# CC2530.net
KiCad netlist of a schematic drawn in Altium Designer
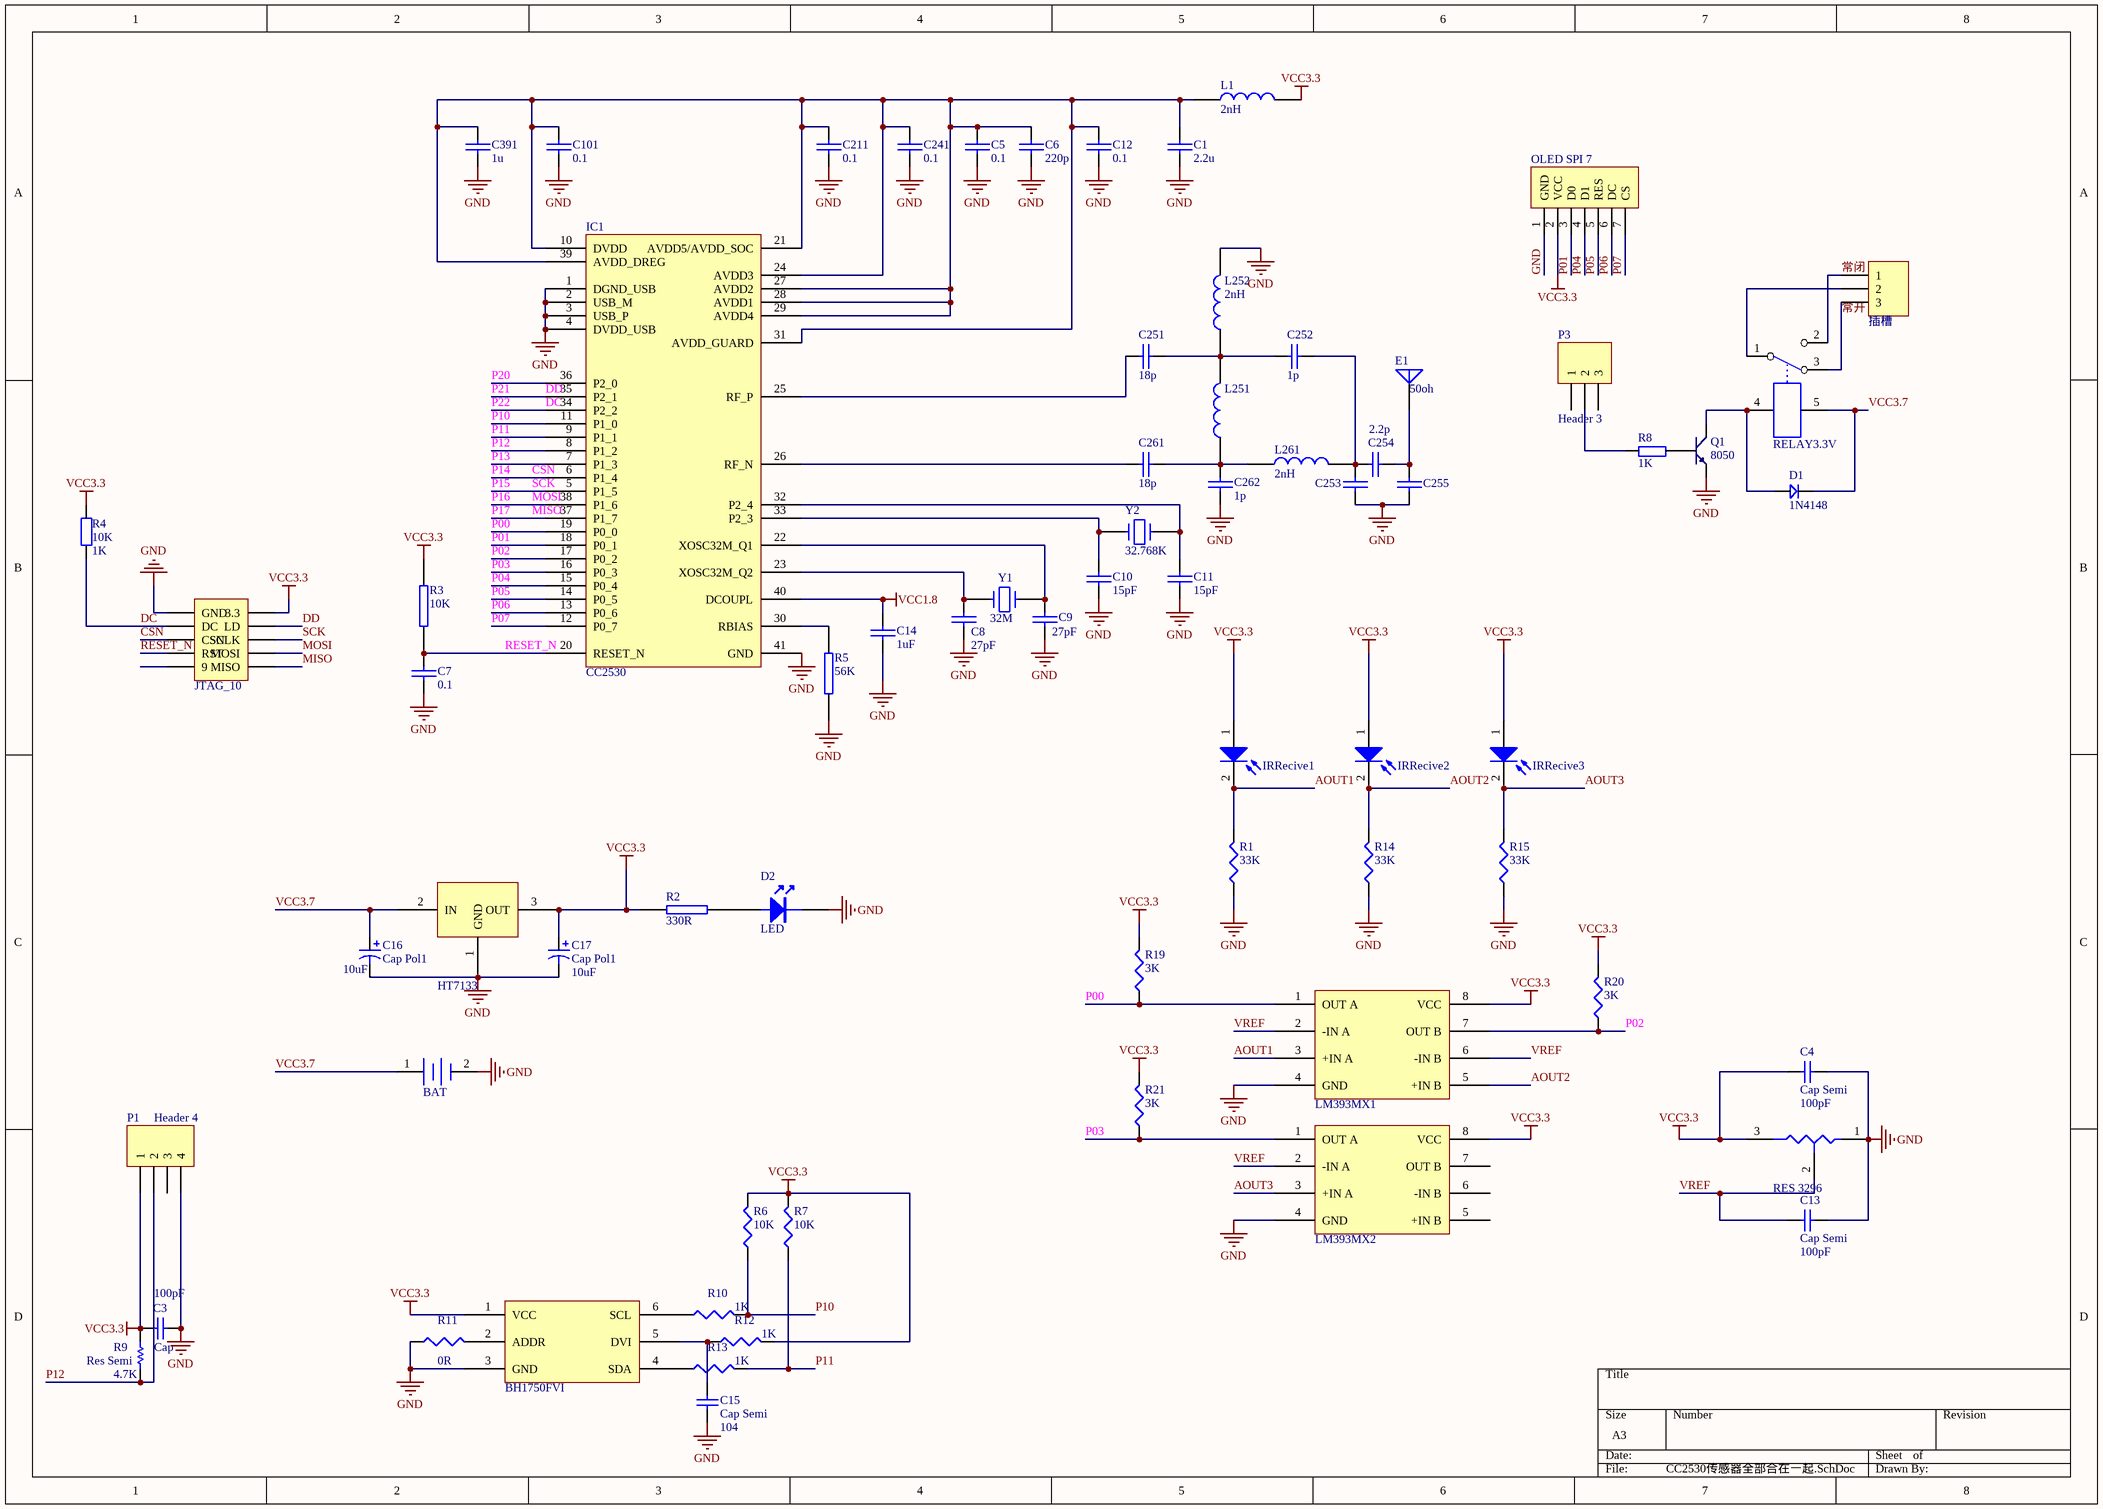
[diagram p0: CC2530传感器全部合在一起.SchDoc]

(export (version "E")
  (design (tool "Eeschema 10.0.6"))
  (components
    (comp (ref "BAT") (value "BAT") (footprint "BAT") (libsource (lib "my Integrated lib ") (part "BAT")))
    (comp (ref "BH1750FVI")
      (value "BH1750FVI")
      (footprint "BH1750FVI")
      (libsource (lib "my Integrated lib ") (part "BH1750FVI"))
    )
    (comp (ref "C1")
      (value "2.2u")
      (footprint "J1-0603")
      (description "Capacitor")
      (libsource (lib "Miscellaneous Devices") (part "CAP"))
    )
    (comp (ref "C3")
      (value "Cap")
      (footprint "J1-0603")
      (description "Capacitor")
      (fields (field (name "ALTIUM_VALUE") "100pF") (field (name "PUBLISHER") "Altium Limited"))
      (libsource (lib "Miscellaneous Devices") (part "Cap"))
    )
    (comp (ref "C4")
      (value "Cap Semi")
      (footprint "3.5X2.8X1.9")
      (description "Capacitor (Semiconductor SIM Model)")
      (fields (field (name "ALTIUM_VALUE") "100pF") (field (name "PUBLISHER") "Altium Limited"))
      (libsource (lib "Miscellaneous Devices") (part "Cap Semi"))
    )
    (comp (ref "C5")
      (value "0.1")
      (footprint "J1-0603")
      (description "Capacitor")
      (libsource (lib "Miscellaneous Devices") (part "CAP"))
    )
    (comp (ref "C6")
      (value "220p")
      (footprint "J1-0603")
      (description "Capacitor")
      (libsource (lib "Miscellaneous Devices") (part "CAP"))
    )
    (comp (ref "C7")
      (value "0.1")
      (footprint "J1-0603")
      (description "Capacitor")
      (libsource (lib "Miscellaneous Devices") (part "CAP"))
    )
    (comp (ref "C8")
      (value "27pF")
      (footprint "J1-0603")
      (description "Capacitor")
      (libsource (lib "Miscellaneous Devices") (part "CAP"))
    )
    (comp (ref "C9")
      (value "27pF")
      (footprint "J1-0603")
      (description "Capacitor")
      (libsource (lib "Miscellaneous Devices") (part "CAP"))
    )
    (comp (ref "C10")
      (value "15pF")
      (footprint "J1-0603")
      (description "Capacitor")
      (libsource (lib "Miscellaneous Devices") (part "CAP"))
    )
    (comp (ref "C11")
      (value "15pF")
      (footprint "J1-0603")
      (description "Capacitor")
      (libsource (lib "Miscellaneous Devices") (part "CAP"))
    )
    (comp (ref "C12")
      (value "0.1")
      (footprint "J1-0603")
      (description "Capacitor")
      (libsource (lib "Miscellaneous Devices") (part "CAP"))
    )
    (comp (ref "C13")
      (value "Cap Semi")
      (footprint "3.5X2.8X1.9")
      (description "Capacitor (Semiconductor SIM Model)")
      (fields (field (name "ALTIUM_VALUE") "100pF") (field (name "PUBLISHER") "Altium Limited"))
      (libsource (lib "Miscellaneous Devices") (part "Cap Semi"))
    )
    (comp (ref "C14")
      (value "1uF")
      (footprint "J1-0603")
      (description "Capacitor")
      (libsource (lib "Miscellaneous Devices") (part "CAP"))
    )
    (comp (ref "C15")
      (value "Cap Semi")
      (footprint "3.5X2.8X1.9")
      (description "Capacitor (Semiconductor SIM Model)")
      (fields (field (name "ALTIUM_VALUE") "104") (field (name "PUBLISHER") "Altium Limited"))
      (libsource (lib "Miscellaneous Devices") (part "Cap Semi"))
    )
    (comp (ref "C16")
      (value "Cap Pol1")
      (footprint "3.5X2.8X1.9")
      (description "Polarized Capacitor (Radial)")
      (fields (field (name "ALTIUM_VALUE") "10uF") (field (name "PUBLISHER") "Altium Limited"))
      (libsource (lib "Miscellaneous Devices") (part "Cap Pol1"))
    )
    (comp (ref "C17")
      (value "Cap Pol1")
      (footprint "3.5X2.8X1.9")
      (description "Polarized Capacitor (Radial)")
      (fields (field (name "ALTIUM_VALUE") "10uF") (field (name "PUBLISHER") "Altium Limited"))
      (libsource (lib "Miscellaneous Devices") (part "Cap Pol1"))
    )
    (comp (ref "C101")
      (value "0.1")
      (footprint "J1-0603")
      (description "Capacitor")
      (libsource (lib "Miscellaneous Devices") (part "CAP"))
    )
    (comp (ref "C211")
      (value "0.1")
      (footprint "J1-0603")
      (description "Capacitor")
      (libsource (lib "Miscellaneous Devices") (part "CAP"))
    )
    (comp (ref "C241")
      (value "0.1")
      (footprint "J1-0603")
      (description "Capacitor")
      (libsource (lib "Miscellaneous Devices") (part "CAP"))
    )
    (comp (ref "C251")
      (value "18p")
      (footprint "J1-0603")
      (description "Capacitor")
      (libsource (lib "Miscellaneous Devices") (part "CAP"))
    )
    (comp (ref "C252")
      (value "1p")
      (footprint "J1-0603")
      (description "Capacitor")
      (libsource (lib "Miscellaneous Devices") (part "CAP"))
    )
    (comp (ref "C253")
      (value "~")
      (footprint "J1-0603")
      (description "Capacitor")
      (libsource (lib "Miscellaneous Devices") (part "CAP"))
    )
    (comp (ref "C254")
      (value "2.2p")
      (footprint "J1-0603")
      (description "Capacitor")
      (libsource (lib "Miscellaneous Devices") (part "CAP"))
    )
    (comp (ref "C255")
      (value "~")
      (footprint "J1-0603")
      (description "Capacitor")
      (libsource (lib "Miscellaneous Devices") (part "CAP"))
    )
    (comp (ref "C261")
      (value "18p")
      (footprint "J1-0603")
      (description "Capacitor")
      (libsource (lib "Miscellaneous Devices") (part "CAP"))
    )
    (comp (ref "C262")
      (value "1p")
      (footprint "J1-0603")
      (description "Capacitor")
      (libsource (lib "Miscellaneous Devices") (part "CAP"))
    )
    (comp (ref "C391")
      (value "1u")
      (footprint "J1-0603")
      (description "Capacitor")
      (libsource (lib "Miscellaneous Devices") (part "CAP"))
    )
    (comp (ref "D1") (value "1N4148") (footprint "C1206") (libsource (lib "my Integrated lib ") (part "D")))
    (comp (ref "D2")
      (value "LED")
      (footprint "3.2X1.6X1.1")
      (libsource (lib "Miscellaneous Devices") (part "LED"))
    )
    (comp (ref "E1")
      (value "50oh")
      (footprint "ANT")
      (description "Generic Antenna")
      (libsource (lib "Miscellaneous Devices") (part "ANTENNA"))
    )
    (comp (ref "HT7133")
      (value "HT7133")
      (footprint "HT7133")
      (libsource (lib "my Integrated lib ") (part "HT7133"))
    )
    (comp (ref "IC1") (value "CC2530") (footprint "QFN40_RHA") (libsource (lib "集成") (part "CC2530")))
    (comp (ref "IRRecive1")
      (value "IRRecive")
      (footprint "IRRecive")
      (libsource (lib "my Integrated lib ") (part "IRRecive"))
    )
    (comp (ref "IRRecive2")
      (value "IRRecive")
      (footprint "IRRecive")
      (libsource (lib "my Integrated lib ") (part "IRRecive"))
    )
    (comp (ref "IRRecive3")
      (value "IRRecive")
      (footprint "IRRecive")
      (libsource (lib "my Integrated lib ") (part "IRRecive"))
    )
    (comp (ref "JTAG_10")
      (value "JTAG_10")
      (footprint "JTAG_10")
      (libsource (lib "my Integrated lib ") (part "JTAG_10"))
    )
    (comp (ref "L1")
      (value "2nH")
      (footprint "J1-0603")
      (libsource (lib "Miscellaneous Devices") (part "INDUCTOR"))
    )
    (comp (ref "L251")
      (value "~")
      (footprint "J1-0603")
      (libsource (lib "Miscellaneous Devices") (part "INDUCTOR"))
    )
    (comp (ref "L252")
      (value "2nH")
      (footprint "J1-0603")
      (libsource (lib "Miscellaneous Devices") (part "INDUCTOR"))
    )
    (comp (ref "L261")
      (value "2nH")
      (footprint "J1-0603")
      (libsource (lib "Miscellaneous Devices") (part "INDUCTOR"))
    )
    (comp (ref "LM393MX1")
      (value "LM393MX")
      (footprint "LM393MX")
      (libsource (lib "my Integrated lib ") (part "LM393MX"))
    )
    (comp (ref "LM393MX2")
      (value "LM393MX")
      (footprint "LM393MX")
      (libsource (lib "my Integrated lib ") (part "LM393MX"))
    )
    (comp (ref "OLED SPI 7")
      (value "OLED SPI 7")
      (footprint "OLED SPI 7")
      (libsource (lib "my Integrated lib ") (part "OLED SPI 7"))
    )
    (comp (ref "P1")
      (value "Header 4")
      (footprint "HDR1X4")
      (description "Header, 4-Pin")
      (fields (field (name "PUBLISHER") "Altium Limited"))
      (libsource (lib "Miscellaneous Connectors") (part "Header 4"))
    )
    (comp (ref "P3")
      (value "Header 3")
      (footprint "HDR1X3")
      (description "Header, 3-Pin")
      (fields (field (name "PUBLISHER") "Altium Limited"))
      (libsource (lib "Miscellaneous Connectors") (part "Header 3"))
    )
    (comp (ref "Q1")
      (value "8050")
      (footprint "SOT-23R")
      (description "8050/BCW846/BCW847")
      (libsource (lib "my Integrated lib ") (part "NPN"))
    )
    (comp (ref "R1")
      (value "33K")
      (footprint "J1-0603")
      (description "Resistor")
      (fields (field (name "Comment") "Res3") (field (name "PUBLISHER") "Altium Limited"))
      (libsource (lib "Miscellaneous Devices") (part "Res3"))
    )
    (comp (ref "R2")
      (value "330R")
      (footprint "J1-0603")
      (libsource (lib "Miscellaneous Devices") (part "RES2"))
    )
    (comp (ref "R3")
      (value "10K")
      (footprint "J1-0603")
      (libsource (lib "Miscellaneous Devices") (part "RES2"))
    )
    (comp (ref "R4")
      (value "10K")
      (footprint "J1-0603")
      (fields (field (name "ALTIUM_VALUE") "1K"))
      (libsource (lib "集成库") (part "res0402"))
    )
    (comp (ref "R5")
      (value "56K")
      (footprint "J1-0603")
      (libsource (lib "Miscellaneous Devices") (part "RES2"))
    )
    (comp (ref "R6")
      (value "10K")
      (footprint "J1-0603")
      (description "Resistor")
      (fields (field (name "Comment") "Res3") (field (name "PUBLISHER") "Altium Limited"))
      (libsource (lib "Miscellaneous Devices") (part "Res3"))
    )
    (comp (ref "R7")
      (value "10K")
      (footprint "J1-0603")
      (description "Resistor")
      (fields (field (name "Comment") "Res3") (field (name "PUBLISHER") "Altium Limited"))
      (libsource (lib "Miscellaneous Devices") (part "Res3"))
    )
    (comp (ref "R8") (value "1K") (footprint "J1-0603") (libsource (lib "my Integrated lib ") (part "R")))
    (comp (ref "R9")
      (value "Res Semi")
      (footprint "J1-0603")
      (description "Semiconductor Resistor")
      (fields (field (name "ALTIUM_VALUE") "4.7K") (field (name "PUBLISHER") "Altium Limited"))
      (libsource (lib "Miscellaneous Devices") (part "Res Semi"))
    )
    (comp (ref "R10")
      (value "1K")
      (footprint "J1-0603")
      (description "Resistor")
      (fields (field (name "Comment") "Res3") (field (name "PUBLISHER") "Altium Limited"))
      (libsource (lib "Miscellaneous Devices") (part "Res3"))
    )
    (comp (ref "R11")
      (value "0R")
      (footprint "J1-0603")
      (description "Resistor")
      (fields (field (name "Comment") "Res3") (field (name "PUBLISHER") "Altium Limited"))
      (libsource (lib "Miscellaneous Devices") (part "Res3"))
    )
    (comp (ref "R12")
      (value "1K")
      (footprint "J1-0603")
      (description "Resistor")
      (fields (field (name "Comment") "Res3") (field (name "PUBLISHER") "Altium Limited"))
      (libsource (lib "Miscellaneous Devices") (part "Res3"))
    )
    (comp (ref "R13")
      (value "1K")
      (footprint "J1-0603")
      (description "Resistor")
      (fields (field (name "Comment") "Res3") (field (name "PUBLISHER") "Altium Limited"))
      (libsource (lib "Miscellaneous Devices") (part "Res3"))
    )
    (comp (ref "R14")
      (value "33K")
      (footprint "J1-0603")
      (description "Resistor")
      (fields (field (name "Comment") "Res3") (field (name "PUBLISHER") "Altium Limited"))
      (libsource (lib "Miscellaneous Devices") (part "Res3"))
    )
    (comp (ref "R15")
      (value "33K")
      (footprint "J1-0603")
      (description "Resistor")
      (fields (field (name "Comment") "Res3") (field (name "PUBLISHER") "Altium Limited"))
      (libsource (lib "Miscellaneous Devices") (part "Res3"))
    )
    (comp (ref "R19")
      (value "3K")
      (footprint "J1-0603")
      (description "Resistor")
      (fields (field (name "Comment") "Res3") (field (name "PUBLISHER") "Altium Limited"))
      (libsource (lib "Miscellaneous Devices") (part "Res3"))
    )
    (comp (ref "R20")
      (value "3K")
      (footprint "J1-0603")
      (description "Resistor")
      (fields (field (name "Comment") "Res3") (field (name "PUBLISHER") "Altium Limited"))
      (libsource (lib "Miscellaneous Devices") (part "Res3"))
    )
    (comp (ref "R21")
      (value "3K")
      (footprint "J1-0603")
      (description "Resistor")
      (fields (field (name "Comment") "Res3") (field (name "PUBLISHER") "Altium Limited"))
      (libsource (lib "Miscellaneous Devices") (part "Res3"))
    )
    (comp (ref "RELAY3.3V")
      (value "RELAY3.3V")
      (footprint "RELAY3.3V")
      (libsource (lib "my Integrated lib ") (part "RELAY3.3V"))
    )
    (comp (ref "RES 3296")
      (value "RES 3296")
      (footprint "RES 3296")
      (libsource (lib "my Integrated lib ") (part "RES 3296"))
    )
    (comp (ref "Y1")
      (value "32M")
      (footprint "XTAL_US")
      (description "Crystal")
      (libsource (lib "Miscellaneous Devices") (part "CRYSTAL"))
    )
    (comp (ref "Y2")
      (value "32.768K")
      (footprint "XTAL 32M")
      (description "Crystal")
      (libsource (lib "Miscellaneous Devices") (part "CRYSTAL"))
    )
    (comp (ref "插槽") (value "插槽") (footprint "杜邦线插槽") (libsource (lib "my Integrated lib ") (part "插槽")))
  )
  (nets
    (net (code "1") (name "/AOUT1") (class "Default")
      (node (ref "IRRecive1") (pin "2") (pinfunction "K_2") (pintype "passive"))
      (node (ref "LM393MX1") (pin "3") (pinfunction "+IN_A_3") (pintype "passive"))
      (node (ref "R1") (pin "2") (pinfunction "2_2") (pintype "passive"))
    )
    (net (code "2") (name "/AOUT2") (class "Default")
      (node (ref "IRRecive2") (pin "2") (pinfunction "K_2") (pintype "passive"))
      (node (ref "LM393MX1") (pin "5") (pinfunction "+IN_B_5") (pintype "passive"))
      (node (ref "R14") (pin "2") (pinfunction "2_2") (pintype "passive"))
    )
    (net (code "3") (name "/AOUT3") (class "Default")
      (node (ref "IRRecive3") (pin "2") (pinfunction "K_2") (pintype "passive"))
      (node (ref "LM393MX2") (pin "3") (pinfunction "+IN_A_3") (pintype "passive"))
      (node (ref "R15") (pin "2") (pinfunction "2_2") (pintype "passive"))
    )
    (net (code "4") (name "/CSN") (class "Default")
      (node (ref "IC1") (pin "6") (pinfunction "P1_4_6") (pintype "passive"))
      (node (ref "JTAG_10") (pin "5") (pinfunction "CSN_5") (pintype "passive"))
    )
    (net (code "5") (name "/DC") (class "Default")
      (node (ref "IC1") (pin "34") (pinfunction "P2_2_34") (pintype "passive"))
      (node (ref "JTAG_10") (pin "3") (pinfunction "DC_3") (pintype "passive"))
      (node (ref "R4") (pin "1") (pinfunction "1_1") (pintype "passive"))
    )
    (net (code "6") (name "/DD") (class "Default")
      (node (ref "IC1") (pin "35") (pinfunction "P2_1_35") (pintype "passive"))
      (node (ref "JTAG_10") (pin "4") (pinfunction "LD_4") (pintype "passive"))
    )
    (net (code "7") (name "/MISO") (class "Default")
      (node (ref "IC1") (pin "37") (pinfunction "P1_7_37") (pintype "passive"))
      (node (ref "JTAG_10") (pin "10") (pinfunction "MISO_10") (pintype "passive"))
    )
    (net (code "8") (name "/MOSI") (class "Default")
      (node (ref "IC1") (pin "38") (pinfunction "P1_6_38") (pintype "passive"))
      (node (ref "JTAG_10") (pin "8") (pinfunction "MOSI_8") (pintype "passive"))
    )
    (net (code "9") (name "/P00") (class "Default")
      (node (ref "IC1") (pin "19") (pinfunction "P0_0_19") (pintype "passive"))
      (node (ref "LM393MX1") (pin "1") (pinfunction "OUT_A_1") (pintype "passive"))
      (node (ref "R19") (pin "1") (pinfunction "1_1") (pintype "passive"))
    )
    (net (code "10") (name "/P01") (class "Default")
      (node (ref "IC1") (pin "18") (pinfunction "P0_1_18") (pintype "passive"))
      (node (ref "OLED SPI 7") (pin "3") (pinfunction "D0_3") (pintype "passive"))
    )
    (net (code "11") (name "/P02") (class "Default")
      (node (ref "IC1") (pin "17") (pinfunction "P0_2_17") (pintype "passive"))
      (node (ref "LM393MX1") (pin "7") (pinfunction "OUT_B_7") (pintype "passive"))
      (node (ref "R20") (pin "1") (pinfunction "1_1") (pintype "passive"))
    )
    (net (code "12") (name "/P03") (class "Default")
      (node (ref "IC1") (pin "16") (pinfunction "P0_3_16") (pintype "passive"))
      (node (ref "LM393MX2") (pin "1") (pinfunction "OUT_A_1") (pintype "passive"))
      (node (ref "R21") (pin "1") (pinfunction "1_1") (pintype "passive"))
    )
    (net (code "13") (name "/P04") (class "Default")
      (node (ref "IC1") (pin "15") (pinfunction "P0_4_15") (pintype "passive"))
      (node (ref "OLED SPI 7") (pin "4") (pinfunction "D1_4") (pintype "passive"))
    )
    (net (code "14") (name "/P05") (class "Default")
      (node (ref "IC1") (pin "14") (pinfunction "P0_5_14") (pintype "passive"))
      (node (ref "OLED SPI 7") (pin "5") (pinfunction "RES_5") (pintype "passive"))
    )
    (net (code "15") (name "/P06") (class "Default")
      (node (ref "IC1") (pin "13") (pinfunction "P0_6_13") (pintype "passive"))
      (node (ref "OLED SPI 7") (pin "6") (pinfunction "DC_6") (pintype "passive"))
    )
    (net (code "16") (name "/P07") (class "Default")
      (node (ref "IC1") (pin "12") (pinfunction "P0_7_12") (pintype "passive"))
      (node (ref "OLED SPI 7") (pin "7") (pinfunction "CS_7") (pintype "passive"))
    )
    (net (code "17") (name "/P10") (class "Default")
      (node (ref "IC1") (pin "11") (pinfunction "P1_0_11") (pintype "passive"))
      (node (ref "R10") (pin "2") (pinfunction "2_2") (pintype "passive"))
      (node (ref "R6") (pin "1") (pinfunction "1_1") (pintype "passive"))
    )
    (net (code "18") (name "/P11") (class "Default")
      (node (ref "IC1") (pin "9") (pinfunction "P1_1_9") (pintype "passive"))
      (node (ref "R13") (pin "2") (pinfunction "2_2") (pintype "passive"))
      (node (ref "R7") (pin "1") (pinfunction "1_1") (pintype "passive"))
    )
    (net (code "19") (name "/P12") (class "Default")
      (node (ref "IC1") (pin "8") (pinfunction "P1_2_8") (pintype "passive"))
      (node (ref "P1") (pin "2") (pinfunction "2_2") (pintype "passive"))
      (node (ref "R9") (pin "1") (pinfunction "1_1") (pintype "passive"))
    )
    (net (code "20") (name "/P13") (class "Default")
      (node (ref "IC1") (pin "7") (pinfunction "P1_3_7") (pintype "passive"))
    )
    (net (code "21") (name "/P15") (class "Default")
      (node (ref "IC1") (pin "5") (pinfunction "P1_5_5") (pintype "passive"))
      (node (ref "JTAG_10") (pin "6") (pinfunction "SCLK_6") (pintype "passive"))
    )
    (net (code "22") (name "/P20") (class "Default")
      (node (ref "IC1") (pin "36") (pinfunction "P2_0_36") (pintype "passive"))
    )
    (net (code "23") (name "/RESET_N") (class "Default")
      (node (ref "C7") (pin "1") (pinfunction "1_1") (pintype "passive"))
      (node (ref "IC1") (pin "20") (pinfunction "RESET_N_20") (pintype "passive"))
      (node (ref "JTAG_10") (pin "7") (pinfunction "RST_7") (pintype "passive"))
      (node (ref "R3") (pin "1") (pinfunction "1_1") (pintype "passive"))
    )
    (net (code "24") (name "/VCC3.7") (class "Default")
      (node (ref "BAT") (pin "1") (pinfunction "+_1") (pintype "passive"))
      (node (ref "C16") (pin "1") (pinfunction "1_1") (pintype "passive"))
      (node (ref "D1") (pin "2") (pintype "passive"))
      (node (ref "HT7133") (pin "2") (pinfunction "IN_2") (pintype "passive"))
      (node (ref "RELAY3.3V") (pin "5") (pinfunction "5_5") (pintype "passive"))
    )
    (net (code "25") (name "/VREF") (class "Default")
      (node (ref "C13") (pin "1") (pinfunction "1_1") (pintype "passive"))
      (node (ref "LM393MX1") (pin "2") (pinfunction "-IN_A_2") (pintype "passive"))
      (node (ref "LM393MX1") (pin "6") (pinfunction "-IN_B_6") (pintype "passive"))
      (node (ref "LM393MX2") (pin "2") (pinfunction "-IN_A_2") (pintype "passive"))
      (node (ref "RES 3296") (pin "2") (pinfunction "TAP_2") (pintype "passive"))
    )
    (net (code "26") (name "/常开") (class "Default")
      (node (ref "RELAY3.3V") (pin "3") (pinfunction "3_3") (pintype "passive"))
      (node (ref "插槽") (pin "3") (pinfunction "3_3") (pintype "passive"))
    )
    (net (code "27") (name "/常闭") (class "Default")
      (node (ref "RELAY3.3V") (pin "2") (pinfunction "2_2") (pintype "passive"))
      (node (ref "插槽") (pin "1") (pinfunction "1_1") (pintype "passive"))
    )
    (net (code "28") (name "GND") (class "Default")
      (node (ref "BAT") (pin "2") (pinfunction "-_2") (pintype "passive"))
      (node (ref "BH1750FVI") (pin "3") (pinfunction "GND_3") (pintype "passive"))
      (node (ref "C1") (pin "2") (pinfunction "2_2") (pintype "passive"))
      (node (ref "C10") (pin "2") (pinfunction "2_2") (pintype "passive"))
      (node (ref "C101") (pin "2") (pinfunction "2_2") (pintype "passive"))
      (node (ref "C11") (pin "2") (pinfunction "2_2") (pintype "passive"))
      (node (ref "C12") (pin "2") (pinfunction "2_2") (pintype "passive"))
      (node (ref "C13") (pin "2") (pinfunction "2_2") (pintype "passive"))
      (node (ref "C14") (pin "2") (pinfunction "2_2") (pintype "passive"))
      (node (ref "C15") (pin "1") (pinfunction "1_1") (pintype "passive"))
      (node (ref "C16") (pin "2") (pinfunction "2_2") (pintype "passive"))
      (node (ref "C17") (pin "2") (pinfunction "2_2") (pintype "passive"))
      (node (ref "C211") (pin "2") (pinfunction "2_2") (pintype "passive"))
      (node (ref "C241") (pin "2") (pinfunction "2_2") (pintype "passive"))
      (node (ref "C253") (pin "2") (pinfunction "2_2") (pintype "passive"))
      (node (ref "C255") (pin "1") (pinfunction "1_1") (pintype "passive"))
      (node (ref "C262") (pin "2") (pinfunction "2_2") (pintype "passive"))
      (node (ref "C3") (pin "2") (pinfunction "2_2") (pintype "passive"))
      (node (ref "C391") (pin "2") (pinfunction "2_2") (pintype "passive"))
      (node (ref "C4") (pin "2") (pinfunction "2_2") (pintype "passive"))
      (node (ref "C5") (pin "2") (pinfunction "2_2") (pintype "passive"))
      (node (ref "C6") (pin "2") (pinfunction "2_2") (pintype "passive"))
      (node (ref "C7") (pin "2") (pinfunction "2_2") (pintype "passive"))
      (node (ref "C8") (pin "2") (pinfunction "2_2") (pintype "passive"))
      (node (ref "C9") (pin "2") (pinfunction "2_2") (pintype "passive"))
      (node (ref "D2") (pin "K") (pinfunction "2_K") (pintype "passive"))
      (node (ref "HT7133") (pin "1") (pinfunction "GND_1") (pintype "passive"))
      (node (ref "IC1") (pin "1") (pinfunction "DGND_USB_1") (pintype "passive"))
      (node (ref "IC1") (pin "2") (pinfunction "USB_M_2") (pintype "passive"))
      (node (ref "IC1") (pin "3") (pinfunction "USB_P_3") (pintype "passive"))
      (node (ref "IC1") (pin "4") (pinfunction "DVDD_USB_4") (pintype "passive"))
      (node (ref "IC1") (pin "41") (pinfunction "GND_41") (pintype "passive"))
      (node (ref "JTAG_10") (pin "1") (pinfunction "GND_1") (pintype "passive"))
      (node (ref "L252") (pin "2") (pinfunction "2_2") (pintype "passive"))
      (node (ref "LM393MX1") (pin "4") (pinfunction "GND_4") (pintype "passive"))
      (node (ref "LM393MX2") (pin "4") (pinfunction "GND_4") (pintype "passive"))
      (node (ref "OLED SPI 7") (pin "1") (pinfunction "GND_1") (pintype "passive"))
      (node (ref "P1") (pin "4") (pinfunction "4_4") (pintype "passive"))
      (node (ref "Q1") (pin "1") (pinfunction "E_1") (pintype "passive"))
      (node (ref "R1") (pin "1") (pinfunction "1_1") (pintype "passive"))
      (node (ref "R11") (pin "1") (pinfunction "1_1") (pintype "passive"))
      (node (ref "R14") (pin "1") (pinfunction "1_1") (pintype "passive"))
      (node (ref "R15") (pin "1") (pinfunction "1_1") (pintype "passive"))
      (node (ref "R5") (pin "2") (pinfunction "2_2") (pintype "passive"))
      (node (ref "RES 3296") (pin "1") (pinfunction "A_1") (pintype "passive"))
    )
    (net (code "29") (name "Net-(BH1750FVI-ADDR)") (class "Default")
      (node (ref "BH1750FVI") (pin "2") (pinfunction "ADDR_2") (pintype "passive"))
      (node (ref "R11") (pin "2") (pinfunction "2_2") (pintype "passive"))
    )
    (net (code "30") (name "Net-(BH1750FVI-DVI)") (class "Default")
      (node (ref "BH1750FVI") (pin "5") (pinfunction "DVI_5") (pintype "passive"))
      (node (ref "C15") (pin "2") (pinfunction "2_2") (pintype "passive"))
      (node (ref "R12") (pin "1") (pinfunction "1_1") (pintype "passive"))
    )
    (net (code "31") (name "Net-(BH1750FVI-SCL)") (class "Default")
      (node (ref "BH1750FVI") (pin "6") (pinfunction "SCL_6") (pintype "passive"))
      (node (ref "R10") (pin "1") (pinfunction "1_1") (pintype "passive"))
    )
    (net (code "32") (name "Net-(BH1750FVI-SDA)") (class "Default")
      (node (ref "BH1750FVI") (pin "4") (pinfunction "SDA_4") (pintype "passive"))
      (node (ref "R13") (pin "1") (pinfunction "1_1") (pintype "passive"))
    )
    (net (code "33") (name "Net-(C251-Pad2)") (class "Default")
      (node (ref "C251") (pin "2") (pinfunction "2_2") (pintype "passive"))
      (node (ref "C252") (pin "1") (pinfunction "1_1") (pintype "passive"))
      (node (ref "L251") (pin "2") (pinfunction "2_2") (pintype "passive"))
      (node (ref "L252") (pin "1") (pinfunction "1_1") (pintype "passive"))
    )
    (net (code "34") (name "Net-(C252-Pad2)") (class "Default")
      (node (ref "C252") (pin "2") (pinfunction "2_2") (pintype "passive"))
      (node (ref "C253") (pin "1") (pinfunction "1_1") (pintype "passive"))
      (node (ref "C254") (pin "1") (pinfunction "1_1") (pintype "passive"))
      (node (ref "L261") (pin "2") (pinfunction "2_2") (pintype "passive"))
    )
    (net (code "35") (name "Net-(C261-Pad2)") (class "Default")
      (node (ref "C261") (pin "2") (pinfunction "2_2") (pintype "passive"))
      (node (ref "C262") (pin "1") (pinfunction "1_1") (pintype "passive"))
      (node (ref "L251") (pin "1") (pinfunction "1_1") (pintype "passive"))
      (node (ref "L261") (pin "1") (pinfunction "1_1") (pintype "passive"))
    )
    (net (code "36") (name "Net-(D2-1)") (class "Default")
      (node (ref "D2") (pin "A") (pinfunction "1_A") (pintype "passive"))
      (node (ref "R2") (pin "1") (pinfunction "1_1") (pintype "passive"))
    )
    (net (code "37") (name "Net-(E1-A)") (class "Default")
      (node (ref "C254") (pin "2") (pinfunction "2_2") (pintype "passive"))
      (node (ref "C255") (pin "2") (pinfunction "2_2") (pintype "passive"))
      (node (ref "E1") (pin "1") (pinfunction "A_1") (pintype "passive"))
    )
    (net (code "38") (name "Net-(IC1-AVDD1)") (class "Default")
      (node (ref "C1") (pin "1") (pinfunction "1_1") (pintype "passive"))
      (node (ref "C101") (pin "1") (pinfunction "1_1") (pintype "passive"))
      (node (ref "C12") (pin "1") (pinfunction "1_1") (pintype "passive"))
      (node (ref "C211") (pin "1") (pinfunction "1_1") (pintype "passive"))
      (node (ref "C241") (pin "1") (pinfunction "1_1") (pintype "passive"))
      (node (ref "C391") (pin "1") (pinfunction "1_1") (pintype "passive"))
      (node (ref "C5") (pin "1") (pinfunction "1_1") (pintype "passive"))
      (node (ref "C6") (pin "1") (pinfunction "1_1") (pintype "passive"))
      (node (ref "IC1") (pin "10") (pinfunction "DVDD_10") (pintype "passive"))
      (node (ref "IC1") (pin "21") (pinfunction "AVDD5/AVDD_SOC_21") (pintype "passive"))
      (node (ref "IC1") (pin "24") (pinfunction "AVDD3_24") (pintype "passive"))
      (node (ref "IC1") (pin "27") (pinfunction "AVDD2_27") (pintype "passive"))
      (node (ref "IC1") (pin "28") (pinfunction "AVDD1_28") (pintype "passive"))
      (node (ref "IC1") (pin "29") (pinfunction "AVDD4_29") (pintype "passive"))
      (node (ref "IC1") (pin "31") (pinfunction "AVDD_GUARD_31") (pintype "passive"))
      (node (ref "IC1") (pin "39") (pinfunction "AVDD_DREG_39") (pintype "passive"))
      (node (ref "L1") (pin "1") (pinfunction "1_1") (pintype "passive"))
    )
    (net (code "39") (name "Net-(IC1-P2_3)") (class "Default")
      (node (ref "C10") (pin "1") (pinfunction "1_1") (pintype "passive"))
      (node (ref "IC1") (pin "33") (pinfunction "P2_3_33") (pintype "passive"))
      (node (ref "Y2") (pin "2") (pinfunction "2_2") (pintype "passive"))
    )
    (net (code "40") (name "Net-(IC1-P2_4)") (class "Default")
      (node (ref "C11") (pin "1") (pinfunction "1_1") (pintype "passive"))
      (node (ref "IC1") (pin "32") (pinfunction "P2_4_32") (pintype "passive"))
      (node (ref "Y2") (pin "1") (pinfunction "1_1") (pintype "passive"))
    )
    (net (code "41") (name "Net-(IC1-RBIAS)") (class "Default")
      (node (ref "IC1") (pin "30") (pinfunction "RBIAS_30") (pintype "passive"))
      (node (ref "R5") (pin "1") (pinfunction "1_1") (pintype "passive"))
    )
    (net (code "42") (name "Net-(IC1-RF_N)") (class "Default")
      (node (ref "C261") (pin "1") (pinfunction "1_1") (pintype "passive"))
      (node (ref "IC1") (pin "26") (pinfunction "RF_N_26") (pintype "passive"))
    )
    (net (code "43") (name "Net-(IC1-RF_P)") (class "Default")
      (node (ref "C251") (pin "1") (pinfunction "1_1") (pintype "passive"))
      (node (ref "IC1") (pin "25") (pinfunction "RF_P_25") (pintype "passive"))
    )
    (net (code "44") (name "Net-(IC1-XOSC32M_Q1)") (class "Default")
      (node (ref "C9") (pin "1") (pinfunction "1_1") (pintype "passive"))
      (node (ref "IC1") (pin "22") (pinfunction "XOSC32M_Q1_22") (pintype "passive"))
      (node (ref "Y1") (pin "2") (pinfunction "2_2") (pintype "passive"))
    )
    (net (code "45") (name "Net-(IC1-XOSC32M_Q2)") (class "Default")
      (node (ref "C8") (pin "1") (pinfunction "1_1") (pintype "passive"))
      (node (ref "IC1") (pin "23") (pinfunction "XOSC32M_Q2_23") (pintype "passive"))
      (node (ref "Y1") (pin "1") (pinfunction "1_1") (pintype "passive"))
    )
    (net (code "46") (name "Net-(P3-Pad2)") (class "Default")
      (node (ref "P3") (pin "2") (pinfunction "2_2") (pintype "passive"))
      (node (ref "R8") (pin "1") (pintype "passive"))
    )
    (net (code "47") (name "Net-(Q1-B)") (class "Default")
      (node (ref "Q1") (pin "2") (pinfunction "B_2") (pintype "passive"))
      (node (ref "R8") (pin "2") (pintype "passive"))
    )
    (net (code "48") (name "Net-(Q1-C)") (class "Default")
      (node (ref "D1") (pin "1") (pintype "passive"))
      (node (ref "Q1") (pin "3") (pinfunction "C_3") (pintype "passive"))
      (node (ref "RELAY3.3V") (pin "4") (pinfunction "4_4") (pintype "passive"))
    )
    (net (code "49") (name "Net-(RELAY3.3V-Pad1)") (class "Default")
      (node (ref "RELAY3.3V") (pin "1") (pinfunction "1_1") (pintype "passive"))
      (node (ref "插槽") (pin "2") (pinfunction "2_2") (pintype "passive"))
    )
    (net (code "50") (name "VCC1.8") (class "Default")
      (node (ref "C14") (pin "1") (pinfunction "1_1") (pintype "passive"))
      (node (ref "IC1") (pin "40") (pinfunction "DCOUPL_40") (pintype "passive"))
    )
    (net (code "51") (name "VCC3.3") (class "Default")
      (node (ref "BH1750FVI") (pin "1") (pinfunction "VCC_1") (pintype "passive"))
      (node (ref "C17") (pin "1") (pinfunction "1_1") (pintype "passive"))
      (node (ref "C3") (pin "1") (pinfunction "1_1") (pintype "passive"))
      (node (ref "C4") (pin "1") (pinfunction "1_1") (pintype "passive"))
      (node (ref "HT7133") (pin "3") (pinfunction "OUT_3") (pintype "passive"))
      (node (ref "IRRecive1") (pin "1") (pinfunction "A_1") (pintype "passive"))
      (node (ref "IRRecive2") (pin "1") (pinfunction "A_1") (pintype "passive"))
      (node (ref "IRRecive3") (pin "1") (pinfunction "A_1") (pintype "passive"))
      (node (ref "JTAG_10") (pin "2") (pinfunction "3.3_2") (pintype "passive"))
      (node (ref "L1") (pin "2") (pinfunction "2_2") (pintype "passive"))
      (node (ref "LM393MX1") (pin "8") (pinfunction "VCC_8") (pintype "passive"))
      (node (ref "LM393MX2") (pin "8") (pinfunction "VCC_8") (pintype "passive"))
      (node (ref "OLED SPI 7") (pin "2") (pinfunction "VCC_2") (pintype "passive"))
      (node (ref "P1") (pin "1") (pinfunction "1_1") (pintype "passive"))
      (node (ref "R12") (pin "2") (pinfunction "2_2") (pintype "passive"))
      (node (ref "R19") (pin "2") (pinfunction "2_2") (pintype "passive"))
      (node (ref "R2") (pin "2") (pinfunction "2_2") (pintype "passive"))
      (node (ref "R20") (pin "2") (pinfunction "2_2") (pintype "passive"))
      (node (ref "R21") (pin "2") (pinfunction "2_2") (pintype "passive"))
      (node (ref "R3") (pin "2") (pinfunction "2_2") (pintype "passive"))
      (node (ref "R4") (pin "2") (pinfunction "2_2") (pintype "passive"))
      (node (ref "R6") (pin "2") (pinfunction "2_2") (pintype "passive"))
      (node (ref "R7") (pin "2") (pinfunction "2_2") (pintype "passive"))
      (node (ref "R9") (pin "2") (pinfunction "2_2") (pintype "passive"))
      (node (ref "RES 3296") (pin "3") (pinfunction "B_3") (pintype "passive"))
    )
    (net (code "52") (name "unconnected-(JTAG_10-Pad9)") (class "Default")
      (node (ref "JTAG_10") (pin "9") (pinfunction "9_9") (pintype "passive"))
    )
    (net (code "53") (name "unconnected-(LM393MX2-+IN_B-Pad5)") (class "Default")
      (node (ref "LM393MX2") (pin "5") (pinfunction "+IN_B_5") (pintype "passive"))
    )
    (net (code "54") (name "unconnected-(LM393MX2--IN_B-Pad6)") (class "Default")
      (node (ref "LM393MX2") (pin "6") (pinfunction "-IN_B_6") (pintype "passive"))
    )
    (net (code "55") (name "unconnected-(LM393MX2-OUT_B-Pad7)") (class "Default")
      (node (ref "LM393MX2") (pin "7") (pinfunction "OUT_B_7") (pintype "passive"))
    )
    (net (code "56") (name "unconnected-(P1-Pad3)") (class "Default")
      (node (ref "P1") (pin "3") (pinfunction "3_3") (pintype "passive"))
    )
    (net (code "57") (name "unconnected-(P3-Pad1)") (class "Default")
      (node (ref "P3") (pin "1") (pinfunction "1_1") (pintype "passive"))
    )
    (net (code "58") (name "unconnected-(P3-Pad3)") (class "Default")
      (node (ref "P3") (pin "3") (pinfunction "3_3") (pintype "passive"))
    )
  )
)
